# StationRecharge.net
KiCad netlist of a schematic drawn in Altium Designer
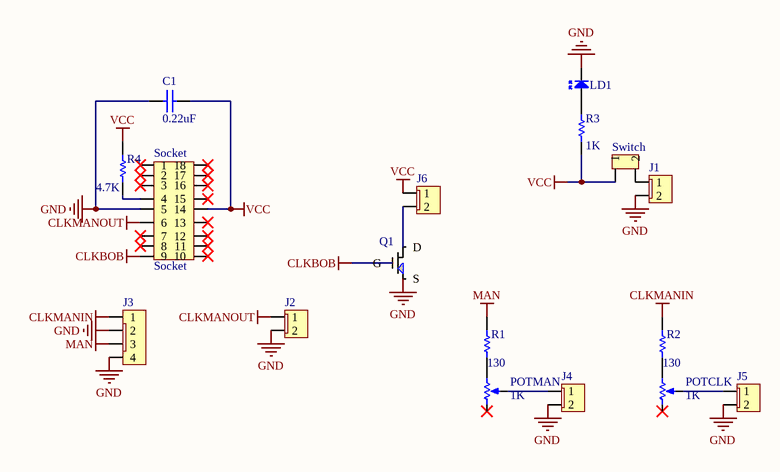
[diagram p0: StationRecharge.SchDoc]

(export (version "E")
  (design (tool "Eeschema 10.0.6"))
  (components
    (comp (ref "C1")
      (value "0.22uF")
      (footprint "CER RAD-0.1")
      (description "Capacitor")
      (fields (field (name "Comment") "Cap Ceramic") (field (name "PUBLISHER") "Altium Limited"))
      (libsource (lib "Lib Sch") (part "Cap Ceramic"))
    )
    (comp (ref "J1")
      (value "Input")
      (footprint "MTA100-2")
      (description "MTA Male 0 Degres")
      (libsource (lib "Lib Sch") (part "MTA100-2"))
    )
    (comp (ref "J2")
      (value "Input")
      (footprint "MTA100-2")
      (description "MTA Male 0 Degres")
      (libsource (lib "Lib Sch") (part "MTA100-2"))
    )
    (comp (ref "J3")
      (value "MTA100-4")
      (footprint "MTA100-4 MF")
      (description "MTA100-4M")
      (libsource (lib "Lib Sch") (part "MTA100-4"))
    )
    (comp (ref "J4")
      (value "Input")
      (footprint "MTA100-2")
      (description "MTA Male 0 Degres")
      (libsource (lib "Lib Sch") (part "MTA100-2"))
    )
    (comp (ref "J5")
      (value "Input")
      (footprint "MTA100-2")
      (description "MTA Male 0 Degres")
      (libsource (lib "Lib Sch") (part "MTA100-2"))
    )
    (comp (ref "J6")
      (value "Input")
      (footprint "MTA100-2")
      (description "MTA Male 0 Degres")
      (libsource (lib "Lib Sch") (part "MTA100-2"))
    )
    (comp (ref "LD1")
      (value "Power Good")
      (footprint "LED 3mm Vertical")
      (description "Through Hole")
      (fields (field (name "PUBLISHER") "Altium Limited"))
      (libsource (lib "Lib Sch") (part "LED 3mm Vertical"))
    )
    (comp (ref "Q1")
      (value "Component_1")
      (footprint "Transistor:PCBComponent_1")
      (libsource (lib "Transistor") (part "Component_1"))
    )
    (comp (ref "R1")
      (value "130")
      (footprint "AXIAL-0.3")
      (description "Resistor")
      (fields (field (name "Comment") "Res1") (field (name "PUBLISHER") "Altium Limited"))
      (libsource (lib "Miscellaneous Devices") (part "Res1"))
    )
    (comp (ref "R2")
      (value "130")
      (footprint "AXIAL-0.3")
      (description "Resistor")
      (fields (field (name "Comment") "Res1") (field (name "PUBLISHER") "Altium Limited"))
      (libsource (lib "Miscellaneous Devices") (part "Res1"))
    )
    (comp (ref "R3")
      (value "1K")
      (footprint "AXIAL-0.3")
      (description "Resistor")
      (fields (field (name "Comment") "Res1") (field (name "PUBLISHER") "Altium Limited"))
      (libsource (lib "Miscellaneous Devices") (part "Res1"))
    )
    (comp (ref "R4")
      (value "4.7K")
      (footprint "AXIAL-0.3")
      (description "Resistor")
      (fields (field (name "Comment") "Res1") (field (name "PUBLISHER") "Altium Limited"))
      (libsource (lib "Miscellaneous Devices") (part "Res1"))
    )
    (comp (ref "Socket") (value "Socket") (footprint "DIP18") (libsource (lib "Lib Sch") (part "Socket")))
    (comp (ref "Switch")
      (value "SwitchMini")
      (footprint "PCBComponent_1")
      (libsource (lib "Lib Sch") (part "SwitchMini"))
    )
    (comp (ref "VR1")
      (value "POTMAN")
      (footprint "VR1")
      (fields (field (name "ALTIUM_VALUE") "1K"))
      (libsource (lib "Lib Sch") (part "Res Pot 10T Vertical"))
    )
    (comp (ref "VR2")
      (value "POTCLK")
      (footprint "VR1")
      (fields (field (name "ALTIUM_VALUE") "1K"))
      (libsource (lib "Lib Sch") (part "Res Pot 10T Vertical"))
    )
  )
  (nets
    (net (code "1") (name "CLKBOB") (class "Default")
      (node (ref "Q1") (pin "G") (pinfunction "G_G") (pintype "passive"))
      (node (ref "Socket") (pin "9") (pinfunction "9_9") (pintype "passive"))
    )
    (net (code "2") (name "CLKMANIN") (class "Default")
      (node (ref "J3") (pin "1") (pinfunction "1_1") (pintype "passive"))
      (node (ref "R2") (pin "2") (pinfunction "2_2") (pintype "passive"))
    )
    (net (code "3") (name "CLKMANOUT") (class "Default")
      (node (ref "J2") (pin "1") (pinfunction "1_1") (pintype "passive"))
      (node (ref "Socket") (pin "6") (pinfunction "6_6") (pintype "passive"))
    )
    (net (code "4") (name "GND") (class "Default")
      (node (ref "C1") (pin "1") (pinfunction "1_1") (pintype "passive"))
      (node (ref "J1") (pin "2") (pinfunction "2_2") (pintype "passive"))
      (node (ref "J2") (pin "2") (pinfunction "2_2") (pintype "passive"))
      (node (ref "J3") (pin "2") (pinfunction "2_2") (pintype "passive"))
      (node (ref "J3") (pin "4") (pinfunction "4_4") (pintype "passive"))
      (node (ref "J4") (pin "2") (pinfunction "2_2") (pintype "passive"))
      (node (ref "J5") (pin "2") (pinfunction "2_2") (pintype "passive"))
      (node (ref "LD1") (pin "2") (pinfunction "K_2") (pintype "passive"))
      (node (ref "Q1") (pin "S") (pinfunction "S_S") (pintype "passive"))
      (node (ref "Socket") (pin "5") (pinfunction "5_5") (pintype "passive"))
    )
    (net (code "5") (name "MAN") (class "Default")
      (node (ref "J3") (pin "3") (pinfunction "3_3") (pintype "passive"))
      (node (ref "R1") (pin "2") (pinfunction "2_2") (pintype "passive"))
    )
    (net (code "6") (name "Net-(J1-Pad1)") (class "Default")
      (node (ref "J1") (pin "1") (pinfunction "1_1") (pintype "passive"))
      (node (ref "Switch") (pin "2") (pinfunction "2_2") (pintype "passive"))
    )
    (net (code "7") (name "Net-(J6-Pad2)") (class "Default")
      (node (ref "J6") (pin "2") (pinfunction "2_2") (pintype "passive"))
      (node (ref "Q1") (pin "D") (pinfunction "D_D") (pintype "passive"))
    )
    (net (code "8") (name "Net-(LD1-A)") (class "Default")
      (node (ref "LD1") (pin "1") (pinfunction "A_1") (pintype "passive"))
      (node (ref "R3") (pin "2") (pinfunction "2_2") (pintype "passive"))
    )
    (net (code "9") (name "Net-(R4-Pad1)") (class "Default")
      (node (ref "R4") (pin "1") (pinfunction "1_1") (pintype "passive"))
      (node (ref "Socket") (pin "4") (pinfunction "4_4") (pintype "passive"))
    )
    (net (code "10") (name "Net-(VR1-Bot)") (class "Default")
      (node (ref "R1") (pin "1") (pinfunction "1_1") (pintype "passive"))
      (node (ref "VR1") (pin "3") (pinfunction "Bot_3") (pintype "passive"))
    )
    (net (code "11") (name "Net-(VR1-Tap)") (class "Default")
      (node (ref "J4") (pin "1") (pinfunction "1_1") (pintype "passive"))
      (node (ref "VR1") (pin "2") (pinfunction "Tap_2") (pintype "passive"))
    )
    (net (code "12") (name "Net-(VR2-Bot)") (class "Default")
      (node (ref "R2") (pin "1") (pinfunction "1_1") (pintype "passive"))
      (node (ref "VR2") (pin "3") (pinfunction "Bot_3") (pintype "passive"))
    )
    (net (code "13") (name "Net-(VR2-Tap)") (class "Default")
      (node (ref "J5") (pin "1") (pinfunction "1_1") (pintype "passive"))
      (node (ref "VR2") (pin "2") (pinfunction "Tap_2") (pintype "passive"))
    )
    (net (code "14") (name "VCC") (class "Default")
      (node (ref "C1") (pin "2") (pinfunction "2_2") (pintype "passive"))
      (node (ref "J6") (pin "1") (pinfunction "1_1") (pintype "passive"))
      (node (ref "R3") (pin "1") (pinfunction "1_1") (pintype "passive"))
      (node (ref "R4") (pin "2") (pinfunction "2_2") (pintype "passive"))
      (node (ref "Socket") (pin "14") (pinfunction "14_14") (pintype "passive"))
      (node (ref "Switch") (pin "1") (pinfunction "1_1") (pintype "passive"))
    )
    (net (code "15") (name "unconnected-(Socket-Pad1)") (class "Default")
      (node (ref "Socket") (pin "1") (pinfunction "1_1") (pintype "passive+no_connect"))
    )
    (net (code "16") (name "unconnected-(Socket-Pad2)") (class "Default")
      (node (ref "Socket") (pin "2") (pinfunction "2_2") (pintype "passive+no_connect"))
    )
    (net (code "17") (name "unconnected-(Socket-Pad3)") (class "Default")
      (node (ref "Socket") (pin "3") (pinfunction "3_3") (pintype "passive+no_connect"))
    )
    (net (code "18") (name "unconnected-(Socket-Pad7)") (class "Default")
      (node (ref "Socket") (pin "7") (pinfunction "7_7") (pintype "passive+no_connect"))
    )
    (net (code "19") (name "unconnected-(Socket-Pad8)") (class "Default")
      (node (ref "Socket") (pin "8") (pinfunction "8_8") (pintype "passive+no_connect"))
    )
    (net (code "20") (name "unconnected-(Socket-Pad10)") (class "Default")
      (node (ref "Socket") (pin "10") (pinfunction "10_10") (pintype "passive+no_connect"))
    )
    (net (code "21") (name "unconnected-(Socket-Pad11)") (class "Default")
      (node (ref "Socket") (pin "11") (pinfunction "11_11") (pintype "passive+no_connect"))
    )
    (net (code "22") (name "unconnected-(Socket-Pad12)") (class "Default")
      (node (ref "Socket") (pin "12") (pinfunction "12_12") (pintype "passive+no_connect"))
    )
    (net (code "23") (name "unconnected-(Socket-Pad13)") (class "Default")
      (node (ref "Socket") (pin "13") (pinfunction "13_13") (pintype "passive+no_connect"))
    )
    (net (code "24") (name "unconnected-(Socket-Pad15)") (class "Default")
      (node (ref "Socket") (pin "15") (pinfunction "15_15") (pintype "passive+no_connect"))
    )
    (net (code "25") (name "unconnected-(Socket-Pad16)") (class "Default")
      (node (ref "Socket") (pin "16") (pinfunction "16_16") (pintype "passive+no_connect"))
    )
    (net (code "26") (name "unconnected-(Socket-Pad17)") (class "Default")
      (node (ref "Socket") (pin "17") (pinfunction "17_17") (pintype "passive+no_connect"))
    )
    (net (code "27") (name "unconnected-(Socket-Pad18)") (class "Default")
      (node (ref "Socket") (pin "18") (pinfunction "18_18") (pintype "passive+no_connect"))
    )
    (net (code "28") (name "unconnected-(VR1-Top-Pad1)") (class "Default")
      (node (ref "VR1") (pin "1") (pinfunction "Top_1") (pintype "passive+no_connect"))
    )
    (net (code "29") (name "unconnected-(VR2-Top-Pad1)") (class "Default")
      (node (ref "VR2") (pin "1") (pinfunction "Top_1") (pintype "passive+no_connect"))
    )
  )
)
